# IotaWatt4_8.net
KiCad netlist of a schematic drawn in EAGLE
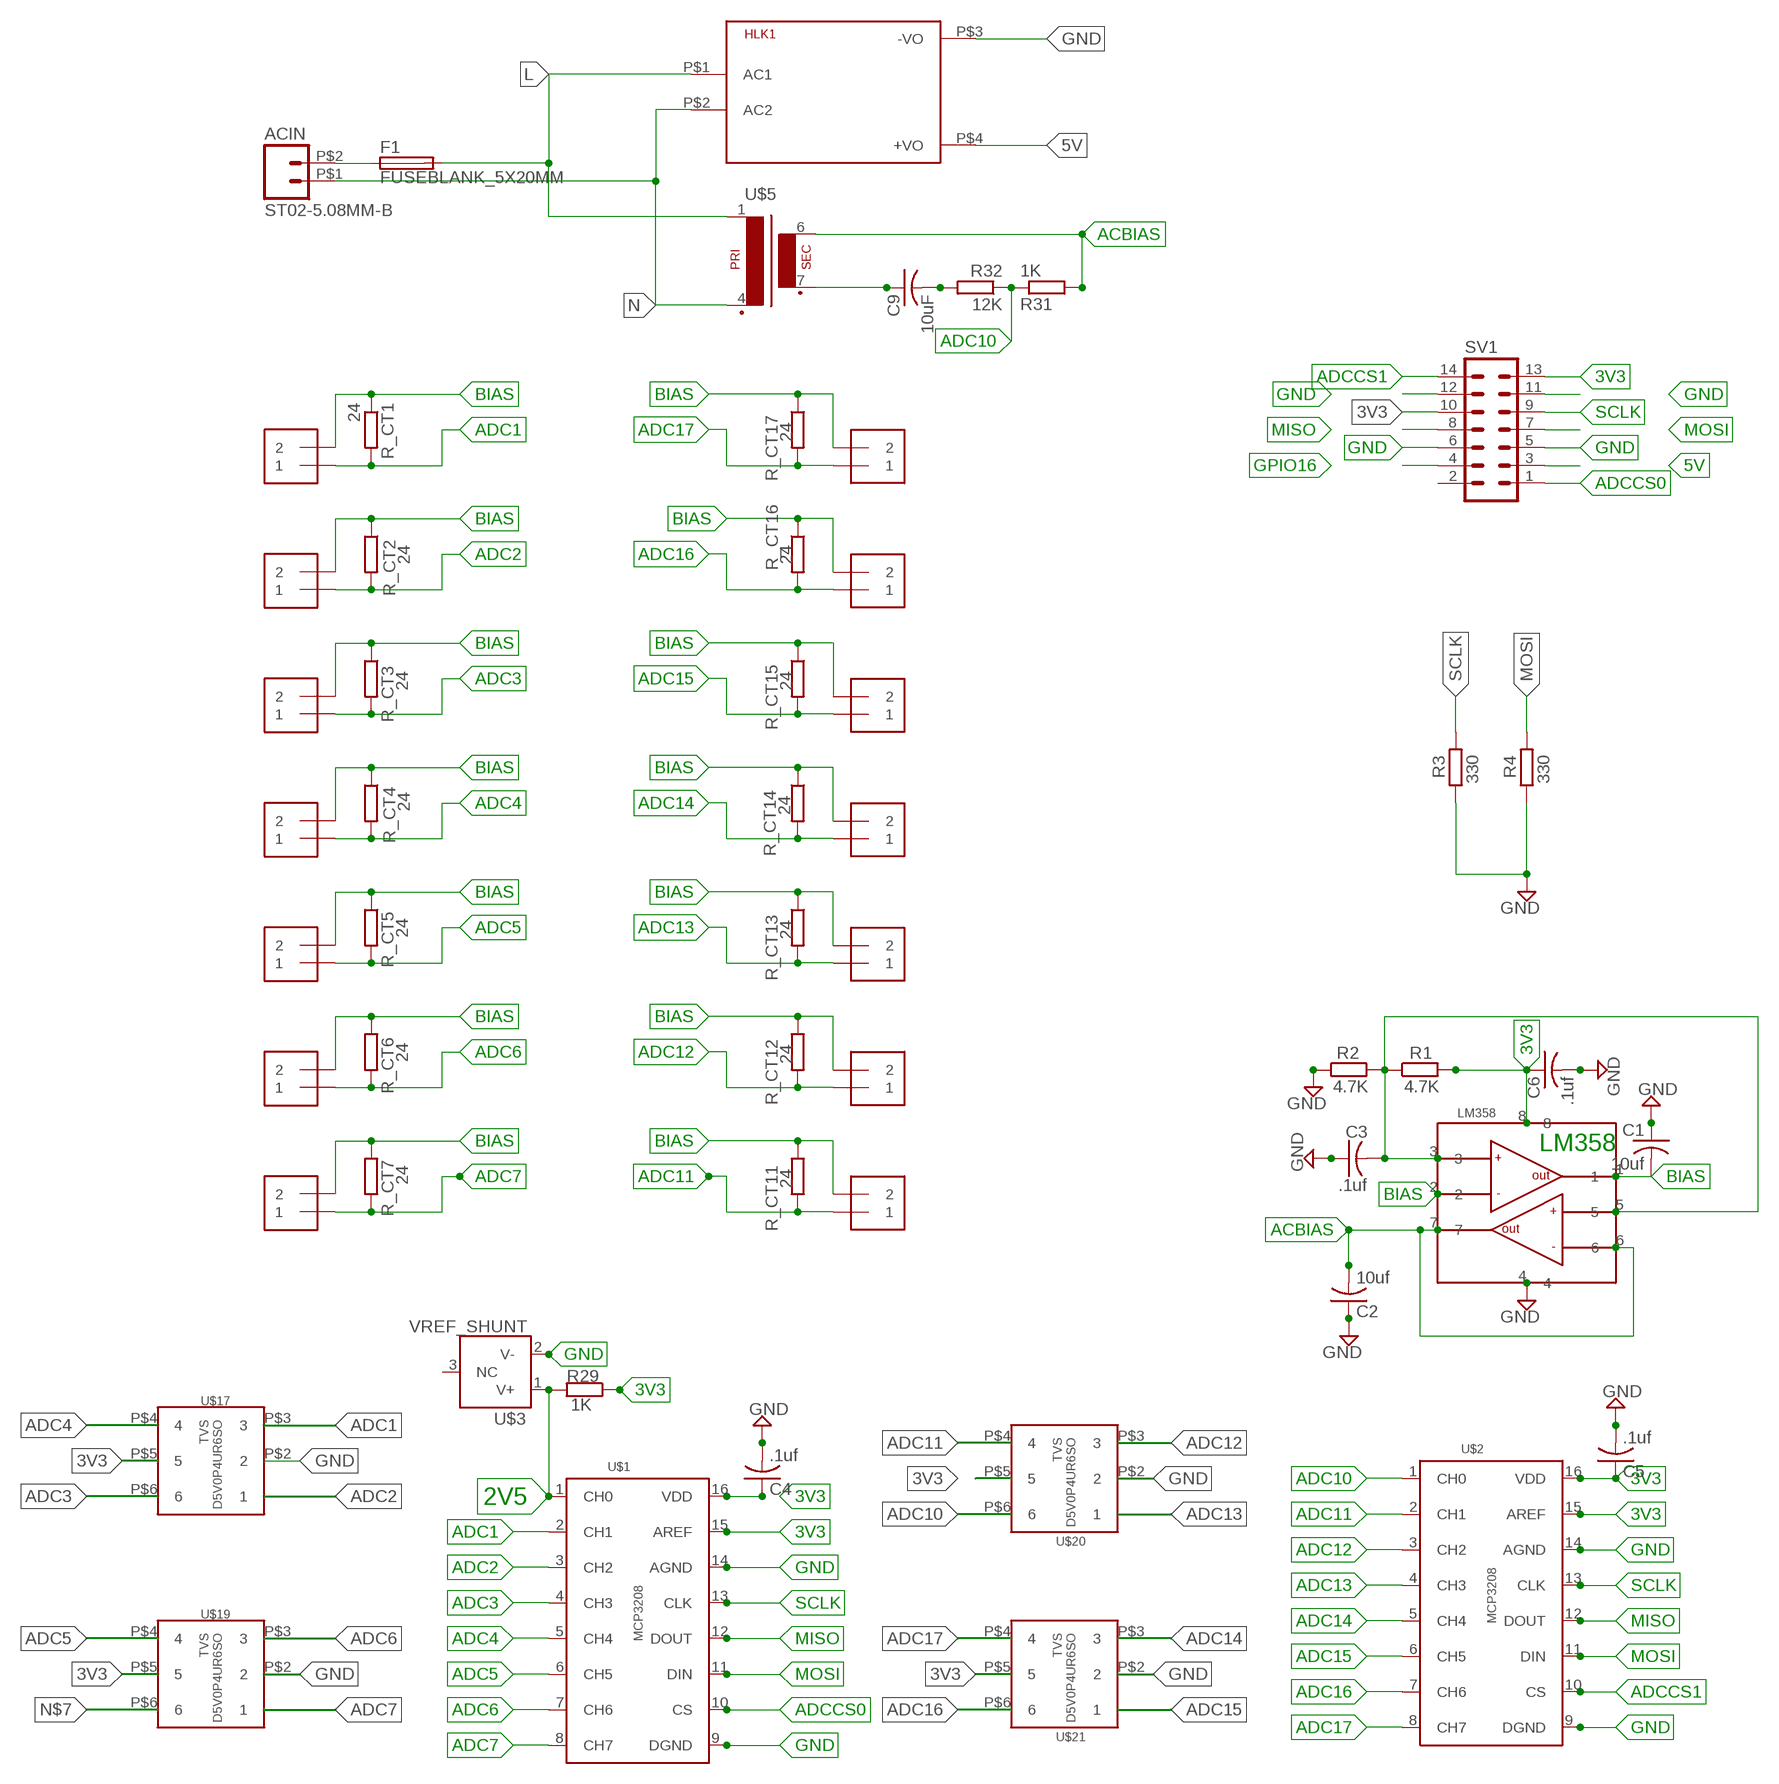
[diagram p0: schematic, sheet 1]

(export (version "E")
  (design (tool "Eeschema 10.0.6"))
  (components
    (comp (ref "ACIN")
      (value "ST02-5.08MM-B")
      (footprint "eagle-import:EK500V4R-B")
      (libsource (lib "eagle-import") (part "ST02-5.08MM-B"))
    )
    (comp (ref "C1")
      (value "10uf")
      (footprint "eagle-import:C0805")
      (libsource (lib "eagle-import") (part "C-USC0805"))
    )
    (comp (ref "C2")
      (value "10uf")
      (footprint "eagle-import:C0805")
      (libsource (lib "eagle-import") (part "C-USC0805"))
    )
    (comp (ref "C3")
      (value ".1uf")
      (footprint "eagle-import:C0805")
      (libsource (lib "eagle-import") (part "C-USC0805"))
    )
    (comp (ref "C4")
      (value ".1uf")
      (footprint "eagle-import:C0805")
      (libsource (lib "eagle-import") (part "C-USC0805"))
    )
    (comp (ref "C5")
      (value ".1uf")
      (footprint "eagle-import:C0805")
      (libsource (lib "eagle-import") (part "C-USC0805"))
    )
    (comp (ref "C6")
      (value ".1uf")
      (footprint "eagle-import:C0805")
      (libsource (lib "eagle-import") (part "C-USC0805"))
    )
    (comp (ref "C9")
      (value "10uF")
      (footprint "eagle-import:C0805")
      (libsource (lib "eagle-import") (part "C-USC0805"))
    )
    (comp (ref "CT1")
      (value "1X2-3.5MM")
      (footprint "eagle-import:3.5MMTERM")
      (libsource (lib "eagle-import") (part "1X2-3.5MM"))
    )
    (comp (ref "CT2")
      (value "1X2-3.5MM")
      (footprint "eagle-import:3.5MMTERM")
      (libsource (lib "eagle-import") (part "1X2-3.5MM"))
    )
    (comp (ref "CT3")
      (value "1X2-3.5MM")
      (footprint "eagle-import:3.5MMTERM")
      (libsource (lib "eagle-import") (part "1X2-3.5MM"))
    )
    (comp (ref "CT4")
      (value "1X2-3.5MM")
      (footprint "eagle-import:3.5MMTERM")
      (libsource (lib "eagle-import") (part "1X2-3.5MM"))
    )
    (comp (ref "CT5")
      (value "1X2-3.5MM")
      (footprint "eagle-import:3.5MMTERM")
      (libsource (lib "eagle-import") (part "1X2-3.5MM"))
    )
    (comp (ref "CT6")
      (value "1X2-3.5MM")
      (footprint "eagle-import:3.5MMTERM")
      (libsource (lib "eagle-import") (part "1X2-3.5MM"))
    )
    (comp (ref "CT7")
      (value "1X2-3.5MM")
      (footprint "eagle-import:3.5MMTERM")
      (libsource (lib "eagle-import") (part "1X2-3.5MM"))
    )
    (comp (ref "CT11")
      (value "1X2-3.5MM")
      (footprint "eagle-import:3.5MMTERM")
      (libsource (lib "eagle-import") (part "1X2-3.5MM"))
    )
    (comp (ref "CT12")
      (value "1X2-3.5MM")
      (footprint "eagle-import:3.5MMTERM")
      (libsource (lib "eagle-import") (part "1X2-3.5MM"))
    )
    (comp (ref "CT13")
      (value "1X2-3.5MM")
      (footprint "eagle-import:3.5MMTERM")
      (libsource (lib "eagle-import") (part "1X2-3.5MM"))
    )
    (comp (ref "CT14")
      (value "1X2-3.5MM")
      (footprint "eagle-import:3.5MMTERM")
      (libsource (lib "eagle-import") (part "1X2-3.5MM"))
    )
    (comp (ref "CT15")
      (value "1X2-3.5MM")
      (footprint "eagle-import:3.5MMTERM")
      (libsource (lib "eagle-import") (part "1X2-3.5MM"))
    )
    (comp (ref "CT16")
      (value "1X2-3.5MM")
      (footprint "eagle-import:3.5MMTERM")
      (libsource (lib "eagle-import") (part "1X2-3.5MM"))
    )
    (comp (ref "CT17")
      (value "1X2-3.5MM")
      (footprint "eagle-import:3.5MMTERM")
      (libsource (lib "eagle-import") (part "1X2-3.5MM"))
    )
    (comp (ref "F1")
      (value "FUSEBLANK_5X20MM")
      (footprint "eagle-import:FUSE_HOLDER_5X20MM")
      (libsource (lib "eagle-import") (part "FUSEBLANK_5X20MM"))
    )
    (comp (ref "HLK1")
      (value "HLK-PM013W")
      (footprint "eagle-import:HLK-PM01")
      (libsource (lib "eagle-import") (part "HLK-PM013W"))
    )
    (comp (ref "R1")
      (value "4.7K")
      (footprint "eagle-import:R0805")
      (libsource (lib "eagle-import") (part "R-EU_R0805"))
    )
    (comp (ref "R2")
      (value "4.7K")
      (footprint "eagle-import:R0805")
      (libsource (lib "eagle-import") (part "R-EU_R0805"))
    )
    (comp (ref "R3")
      (value "330")
      (footprint "eagle-import:R0805")
      (libsource (lib "eagle-import") (part "R-EU_R0805"))
    )
    (comp (ref "R4")
      (value "330")
      (footprint "eagle-import:R0805")
      (libsource (lib "eagle-import") (part "R-EU_R0805"))
    )
    (comp (ref "R29")
      (value "1K")
      (footprint "eagle-import:R0805")
      (libsource (lib "eagle-import") (part "R-EU_R0805"))
    )
    (comp (ref "R31")
      (value "1K")
      (footprint "eagle-import:R0805")
      (libsource (lib "eagle-import") (part "R-EU_R0805"))
    )
    (comp (ref "R32")
      (value "12K")
      (footprint "eagle-import:R0805")
      (libsource (lib "eagle-import") (part "R-EU_R0805"))
    )
    (comp (ref "R_CT1")
      (value "24")
      (footprint "eagle-import:R0805")
      (libsource (lib "eagle-import") (part "R-EU_R0805"))
    )
    (comp (ref "R_CT2")
      (value "24")
      (footprint "eagle-import:R0805")
      (libsource (lib "eagle-import") (part "R-EU_R0805"))
    )
    (comp (ref "R_CT3")
      (value "24")
      (footprint "eagle-import:R0805")
      (libsource (lib "eagle-import") (part "R-EU_R0805"))
    )
    (comp (ref "R_CT4")
      (value "24")
      (footprint "eagle-import:R0805")
      (libsource (lib "eagle-import") (part "R-EU_R0805"))
    )
    (comp (ref "R_CT5")
      (value "24")
      (footprint "eagle-import:R0805")
      (libsource (lib "eagle-import") (part "R-EU_R0805"))
    )
    (comp (ref "R_CT6")
      (value "24")
      (footprint "eagle-import:R0805")
      (libsource (lib "eagle-import") (part "R-EU_R0805"))
    )
    (comp (ref "R_CT7")
      (value "24")
      (footprint "eagle-import:R0805")
      (libsource (lib "eagle-import") (part "R-EU_R0805"))
    )
    (comp (ref "R_CT11")
      (value "24")
      (footprint "eagle-import:R0805")
      (libsource (lib "eagle-import") (part "R-EU_R0805"))
    )
    (comp (ref "R_CT12")
      (value "24")
      (footprint "eagle-import:R0805")
      (libsource (lib "eagle-import") (part "R-EU_R0805"))
    )
    (comp (ref "R_CT13")
      (value "24")
      (footprint "eagle-import:R0805")
      (libsource (lib "eagle-import") (part "R-EU_R0805"))
    )
    (comp (ref "R_CT14")
      (value "24")
      (footprint "eagle-import:R0805")
      (libsource (lib "eagle-import") (part "R-EU_R0805"))
    )
    (comp (ref "R_CT15")
      (value "24")
      (footprint "eagle-import:R0805")
      (libsource (lib "eagle-import") (part "R-EU_R0805"))
    )
    (comp (ref "R_CT16")
      (value "24")
      (footprint "eagle-import:R0805")
      (libsource (lib "eagle-import") (part "R-EU_R0805"))
    )
    (comp (ref "R_CT17")
      (value "24")
      (footprint "eagle-import:R0805")
      (libsource (lib "eagle-import") (part "R-EU_R0805"))
    )
    (comp (ref "SV1")
      (value "MA07-2")
      (footprint "eagle-import:MA07-2")
      (libsource (lib "eagle-import") (part "MA07-2"))
    )
    (comp (ref "U$1")
      (value "MCP3208")
      (footprint "eagle-import:SOIC_16")
      (libsource (lib "eagle-import") (part "MCP3208"))
    )
    (comp (ref "U$2")
      (value "MCP3208")
      (footprint "eagle-import:SOIC_16")
      (libsource (lib "eagle-import") (part "MCP3208"))
    )
    (comp (ref "U$3")
      (value "VREF_SHUNT")
      (footprint "eagle-import:SOT23_3")
      (libsource (lib "eagle-import") (part "VREF_SHUNT"))
    )
    (comp (ref "U$5")
      (value "BV20_1P1S")
      (footprint "eagle-import:BV20")
      (libsource (lib "eagle-import") (part "BV20_1P1S"))
    )
    (comp (ref "U$17")
      (value "TVS_4CHAN_ARRAYSC-74")
      (footprint "eagle-import:SC-74")
      (libsource (lib "eagle-import") (part "TVS_4CHAN_ARRAYSC-74"))
    )
    (comp (ref "U$19")
      (value "TVS_4CHAN_ARRAYSC-74")
      (footprint "eagle-import:SC-74")
      (libsource (lib "eagle-import") (part "TVS_4CHAN_ARRAYSC-74"))
    )
    (comp (ref "U$20")
      (value "TVS_4CHAN_ARRAYSC-74")
      (footprint "eagle-import:SC-74")
      (libsource (lib "eagle-import") (part "TVS_4CHAN_ARRAYSC-74"))
    )
    (comp (ref "U$21")
      (value "TVS_4CHAN_ARRAYSC-74")
      (footprint "eagle-import:SC-74")
      (libsource (lib "eagle-import") (part "TVS_4CHAN_ARRAYSC-74"))
    )
    (comp (ref "U$22")
      (value "LM358_DUAL_OP-AMP")
      (footprint "eagle-import:SOIC_8")
      (libsource (lib "eagle-import") (part "LM358_DUAL_OP-AMP"))
    )
  )
  (nets
    (net (code "1") (name "2V5") (class "Default")
      (node (ref "R29") (pin "2") (pinfunction "2_2") (pintype "passive"))
      (node (ref "U$1") (pin "1") (pinfunction "CH0_1") (pintype "input"))
      (node (ref "U$3") (pin "1") (pinfunction "V+_1") (pintype "bidirectional"))
    )
    (net (code "2") (name "3V3") (class "Default")
      (node (ref "C4") (pin "1") (pinfunction "1_1") (pintype "passive"))
      (node (ref "C5") (pin "1") (pinfunction "1_1") (pintype "passive"))
      (node (ref "C6") (pin "1") (pinfunction "1_1") (pintype "passive"))
      (node (ref "R1") (pin "2") (pinfunction "2_2") (pintype "passive"))
      (node (ref "R29") (pin "1") (pinfunction "1_1") (pintype "passive"))
      (node (ref "SV1") (pin "10") (pinfunction "10_10") (pintype "passive"))
      (node (ref "SV1") (pin "13") (pinfunction "13_13") (pintype "passive"))
      (node (ref "U$1") (pin "15") (pinfunction "AREF_15") (pintype "input"))
      (node (ref "U$1") (pin "16") (pinfunction "VDD_16") (pintype "bidirectional"))
      (node (ref "U$17") (pin "P$5") (pinfunction "5_P$5") (pintype "bidirectional"))
      (node (ref "U$19") (pin "P$5") (pinfunction "5_P$5") (pintype "bidirectional"))
      (node (ref "U$2") (pin "15") (pinfunction "AREF_15") (pintype "input"))
      (node (ref "U$2") (pin "16") (pinfunction "VDD_16") (pintype "bidirectional"))
      (node (ref "U$20") (pin "P$5") (pinfunction "5_P$5") (pintype "bidirectional"))
      (node (ref "U$21") (pin "P$5") (pinfunction "5_P$5") (pintype "bidirectional"))
      (node (ref "U$22") (pin "8") (pinfunction "8_8") (pintype "bidirectional"))
    )
    (net (code "3") (name "5V") (class "Default")
      (node (ref "HLK1") (pin "P$4") (pinfunction "+VO_P$4") (pintype "bidirectional"))
      (node (ref "SV1") (pin "3") (pinfunction "3_3") (pintype "passive"))
    )
    (net (code "4") (name "ACBIAS") (class "Default")
      (node (ref "C2") (pin "2") (pinfunction "2_2") (pintype "passive"))
      (node (ref "R31") (pin "2") (pinfunction "2_2") (pintype "passive"))
      (node (ref "U$22") (pin "6") (pinfunction "6_6") (pintype "bidirectional"))
      (node (ref "U$22") (pin "7") (pinfunction "7_7") (pintype "bidirectional"))
      (node (ref "U$5") (pin "6") (pinfunction "S4_6") (pintype "passive"))
    )
    (net (code "5") (name "ADC1") (class "Default")
      (node (ref "CT1") (pin "1") (pinfunction "1_1") (pintype "passive"))
      (node (ref "R_CT1") (pin "2") (pinfunction "2_2") (pintype "passive"))
      (node (ref "U$1") (pin "2") (pinfunction "CH1_2") (pintype "input"))
      (node (ref "U$17") (pin "P$3") (pinfunction "3_P$3") (pintype "bidirectional"))
    )
    (net (code "6") (name "ADC2") (class "Default")
      (node (ref "CT2") (pin "1") (pinfunction "1_1") (pintype "passive"))
      (node (ref "R_CT2") (pin "2") (pinfunction "2_2") (pintype "passive"))
      (node (ref "U$1") (pin "3") (pinfunction "CH2_3") (pintype "input"))
      (node (ref "U$17") (pin "P$1") (pinfunction "1_P$1") (pintype "bidirectional"))
    )
    (net (code "7") (name "ADC3") (class "Default")
      (node (ref "CT3") (pin "1") (pinfunction "1_1") (pintype "passive"))
      (node (ref "R_CT3") (pin "2") (pinfunction "2_2") (pintype "passive"))
      (node (ref "U$1") (pin "4") (pinfunction "CH3_4") (pintype "input"))
      (node (ref "U$17") (pin "P$6") (pinfunction "6_P$6") (pintype "bidirectional"))
    )
    (net (code "8") (name "ADC4") (class "Default")
      (node (ref "CT4") (pin "1") (pinfunction "1_1") (pintype "passive"))
      (node (ref "R_CT4") (pin "2") (pinfunction "2_2") (pintype "passive"))
      (node (ref "U$1") (pin "5") (pinfunction "CH4_5") (pintype "bidirectional"))
      (node (ref "U$17") (pin "P$4") (pinfunction "4_P$4") (pintype "bidirectional"))
    )
    (net (code "9") (name "ADC5") (class "Default")
      (node (ref "CT5") (pin "1") (pinfunction "1_1") (pintype "passive"))
      (node (ref "R_CT5") (pin "2") (pinfunction "2_2") (pintype "passive"))
      (node (ref "U$1") (pin "6") (pinfunction "CH5_6") (pintype "bidirectional"))
      (node (ref "U$19") (pin "P$4") (pinfunction "4_P$4") (pintype "bidirectional"))
    )
    (net (code "10") (name "ADC6") (class "Default")
      (node (ref "CT6") (pin "1") (pinfunction "1_1") (pintype "passive"))
      (node (ref "R_CT6") (pin "2") (pinfunction "2_2") (pintype "passive"))
      (node (ref "U$1") (pin "7") (pinfunction "CH6_7") (pintype "input"))
      (node (ref "U$19") (pin "P$3") (pinfunction "3_P$3") (pintype "bidirectional"))
    )
    (net (code "11") (name "ADC7") (class "Default")
      (node (ref "CT7") (pin "1") (pinfunction "1_1") (pintype "passive"))
      (node (ref "R_CT7") (pin "2") (pinfunction "2_2") (pintype "passive"))
      (node (ref "U$1") (pin "8") (pinfunction "CH7_8") (pintype "bidirectional"))
      (node (ref "U$19") (pin "P$1") (pinfunction "1_P$1") (pintype "bidirectional"))
    )
    (net (code "12") (name "ADC10") (class "Default")
      (node (ref "R31") (pin "1") (pinfunction "1_1") (pintype "passive"))
      (node (ref "R32") (pin "1") (pinfunction "1_1") (pintype "passive"))
      (node (ref "U$2") (pin "1") (pinfunction "CH0_1") (pintype "input"))
      (node (ref "U$20") (pin "P$6") (pinfunction "6_P$6") (pintype "bidirectional"))
    )
    (net (code "13") (name "ADC11") (class "Default")
      (node (ref "CT11") (pin "1") (pinfunction "1_1") (pintype "passive"))
      (node (ref "R_CT11") (pin "2") (pinfunction "2_2") (pintype "passive"))
      (node (ref "U$2") (pin "2") (pinfunction "CH1_2") (pintype "input"))
      (node (ref "U$20") (pin "P$4") (pinfunction "4_P$4") (pintype "bidirectional"))
    )
    (net (code "14") (name "ADC12") (class "Default")
      (node (ref "CT12") (pin "1") (pinfunction "1_1") (pintype "passive"))
      (node (ref "R_CT12") (pin "2") (pinfunction "2_2") (pintype "passive"))
      (node (ref "U$2") (pin "3") (pinfunction "CH2_3") (pintype "input"))
      (node (ref "U$20") (pin "P$3") (pinfunction "3_P$3") (pintype "bidirectional"))
    )
    (net (code "15") (name "ADC13") (class "Default")
      (node (ref "CT13") (pin "1") (pinfunction "1_1") (pintype "passive"))
      (node (ref "R_CT13") (pin "2") (pinfunction "2_2") (pintype "passive"))
      (node (ref "U$2") (pin "4") (pinfunction "CH3_4") (pintype "input"))
      (node (ref "U$20") (pin "P$1") (pinfunction "1_P$1") (pintype "bidirectional"))
    )
    (net (code "16") (name "ADC14") (class "Default")
      (node (ref "CT14") (pin "1") (pinfunction "1_1") (pintype "passive"))
      (node (ref "R_CT14") (pin "2") (pinfunction "2_2") (pintype "passive"))
      (node (ref "U$2") (pin "5") (pinfunction "CH4_5") (pintype "bidirectional"))
      (node (ref "U$21") (pin "P$3") (pinfunction "3_P$3") (pintype "bidirectional"))
    )
    (net (code "17") (name "ADC15") (class "Default")
      (node (ref "CT15") (pin "1") (pinfunction "1_1") (pintype "passive"))
      (node (ref "R_CT15") (pin "2") (pinfunction "2_2") (pintype "passive"))
      (node (ref "U$2") (pin "6") (pinfunction "CH5_6") (pintype "bidirectional"))
      (node (ref "U$21") (pin "P$1") (pinfunction "1_P$1") (pintype "bidirectional"))
    )
    (net (code "18") (name "ADC16") (class "Default")
      (node (ref "CT16") (pin "1") (pinfunction "1_1") (pintype "passive"))
      (node (ref "R_CT16") (pin "2") (pinfunction "2_2") (pintype "passive"))
      (node (ref "U$2") (pin "7") (pinfunction "CH6_7") (pintype "input"))
      (node (ref "U$21") (pin "P$6") (pinfunction "6_P$6") (pintype "bidirectional"))
    )
    (net (code "19") (name "ADC17") (class "Default")
      (node (ref "CT17") (pin "1") (pinfunction "1_1") (pintype "passive"))
      (node (ref "R_CT17") (pin "2") (pinfunction "2_2") (pintype "passive"))
      (node (ref "U$2") (pin "8") (pinfunction "CH7_8") (pintype "bidirectional"))
      (node (ref "U$21") (pin "P$4") (pinfunction "4_P$4") (pintype "bidirectional"))
    )
    (net (code "20") (name "ADCCS0") (class "Default")
      (node (ref "SV1") (pin "1") (pinfunction "1_1") (pintype "passive"))
      (node (ref "U$1") (pin "10") (pinfunction "CS_10") (pintype "input"))
    )
    (net (code "21") (name "ADCCS1") (class "Default")
      (node (ref "SV1") (pin "14") (pinfunction "14_14") (pintype "passive"))
      (node (ref "U$2") (pin "10") (pinfunction "CS_10") (pintype "input"))
    )
    (net (code "22") (name "BIAS") (class "Default")
      (node (ref "C1") (pin "2") (pinfunction "2_2") (pintype "passive"))
      (node (ref "CT1") (pin "2") (pinfunction "2_2") (pintype "passive"))
      (node (ref "CT11") (pin "2") (pinfunction "2_2") (pintype "passive"))
      (node (ref "CT12") (pin "2") (pinfunction "2_2") (pintype "passive"))
      (node (ref "CT13") (pin "2") (pinfunction "2_2") (pintype "passive"))
      (node (ref "CT14") (pin "2") (pinfunction "2_2") (pintype "passive"))
      (node (ref "CT15") (pin "2") (pinfunction "2_2") (pintype "passive"))
      (node (ref "CT16") (pin "2") (pinfunction "2_2") (pintype "passive"))
      (node (ref "CT17") (pin "2") (pinfunction "2_2") (pintype "passive"))
      (node (ref "CT2") (pin "2") (pinfunction "2_2") (pintype "passive"))
      (node (ref "CT3") (pin "2") (pinfunction "2_2") (pintype "passive"))
      (node (ref "CT4") (pin "2") (pinfunction "2_2") (pintype "passive"))
      (node (ref "CT5") (pin "2") (pinfunction "2_2") (pintype "passive"))
      (node (ref "CT6") (pin "2") (pinfunction "2_2") (pintype "passive"))
      (node (ref "CT7") (pin "2") (pinfunction "2_2") (pintype "passive"))
      (node (ref "R_CT1") (pin "1") (pinfunction "1_1") (pintype "passive"))
      (node (ref "R_CT11") (pin "1") (pinfunction "1_1") (pintype "passive"))
      (node (ref "R_CT12") (pin "1") (pinfunction "1_1") (pintype "passive"))
      (node (ref "R_CT13") (pin "1") (pinfunction "1_1") (pintype "passive"))
      (node (ref "R_CT14") (pin "1") (pinfunction "1_1") (pintype "passive"))
      (node (ref "R_CT15") (pin "1") (pinfunction "1_1") (pintype "passive"))
      (node (ref "R_CT16") (pin "1") (pinfunction "1_1") (pintype "passive"))
      (node (ref "R_CT17") (pin "1") (pinfunction "1_1") (pintype "passive"))
      (node (ref "R_CT2") (pin "1") (pinfunction "1_1") (pintype "passive"))
      (node (ref "R_CT3") (pin "1") (pinfunction "1_1") (pintype "passive"))
      (node (ref "R_CT4") (pin "1") (pinfunction "1_1") (pintype "passive"))
      (node (ref "R_CT5") (pin "1") (pinfunction "1_1") (pintype "passive"))
      (node (ref "R_CT6") (pin "1") (pinfunction "1_1") (pintype "passive"))
      (node (ref "R_CT7") (pin "1") (pinfunction "1_1") (pintype "passive"))
      (node (ref "U$22") (pin "1") (pinfunction "1_1") (pintype "bidirectional"))
      (node (ref "U$22") (pin "2") (pinfunction "2_2") (pintype "bidirectional"))
    )
    (net (code "23") (name "GND") (class "Default")
      (node (ref "C1") (pin "1") (pinfunction "1_1") (pintype "passive"))
      (node (ref "C2") (pin "1") (pinfunction "1_1") (pintype "passive"))
      (node (ref "C3") (pin "1") (pinfunction "1_1") (pintype "passive"))
      (node (ref "C4") (pin "2") (pinfunction "2_2") (pintype "passive"))
      (node (ref "C5") (pin "2") (pinfunction "2_2") (pintype "passive"))
      (node (ref "C6") (pin "2") (pinfunction "2_2") (pintype "passive"))
      (node (ref "HLK1") (pin "P$3") (pinfunction "-VO_P$3") (pintype "bidirectional"))
      (node (ref "R2") (pin "1") (pinfunction "1_1") (pintype "passive"))
      (node (ref "R3") (pin "1") (pinfunction "1_1") (pintype "passive"))
      (node (ref "R4") (pin "1") (pinfunction "1_1") (pintype "passive"))
      (node (ref "SV1") (pin "11") (pinfunction "11_11") (pintype "passive"))
      (node (ref "SV1") (pin "12") (pinfunction "12_12") (pintype "passive"))
      (node (ref "SV1") (pin "5") (pinfunction "5_5") (pintype "passive"))
      (node (ref "SV1") (pin "6") (pinfunction "6_6") (pintype "passive"))
      (node (ref "U$1") (pin "14") (pinfunction "AGND_14") (pintype "input"))
      (node (ref "U$1") (pin "9") (pinfunction "DGND_9") (pintype "bidirectional"))
      (node (ref "U$17") (pin "P$2") (pinfunction "2_P$2") (pintype "bidirectional"))
      (node (ref "U$19") (pin "P$2") (pinfunction "2_P$2") (pintype "bidirectional"))
      (node (ref "U$2") (pin "14") (pinfunction "AGND_14") (pintype "input"))
      (node (ref "U$2") (pin "9") (pinfunction "DGND_9") (pintype "bidirectional"))
      (node (ref "U$20") (pin "P$2") (pinfunction "2_P$2") (pintype "bidirectional"))
      (node (ref "U$21") (pin "P$2") (pinfunction "2_P$2") (pintype "bidirectional"))
      (node (ref "U$22") (pin "4") (pinfunction "4_4") (pintype "bidirectional"))
      (node (ref "U$3") (pin "2") (pinfunction "V-_2") (pintype "bidirectional"))
    )
    (net (code "24") (name "GPIO16") (class "Default")
      (node (ref "SV1") (pin "4") (pinfunction "4_4") (pintype "passive"))
    )
    (net (code "25") (name "L") (class "Default")
      (node (ref "F1") (pin "2") (pinfunction "2_2") (pintype "passive"))
      (node (ref "HLK1") (pin "P$1") (pinfunction "AC1_P$1") (pintype "bidirectional"))
      (node (ref "U$5") (pin "1") (pinfunction "P1_1") (pintype "passive"))
    )
    (net (code "26") (name "MISO") (class "Default")
      (node (ref "SV1") (pin "8") (pinfunction "8_8") (pintype "passive"))
      (node (ref "U$1") (pin "12") (pinfunction "DOUT_12") (pintype "bidirectional"))
      (node (ref "U$2") (pin "12") (pinfunction "DOUT_12") (pintype "bidirectional"))
    )
    (net (code "27") (name "MOSI") (class "Default")
      (node (ref "R4") (pin "2") (pinfunction "2_2") (pintype "passive"))
      (node (ref "SV1") (pin "7") (pinfunction "7_7") (pintype "passive"))
      (node (ref "U$1") (pin "11") (pinfunction "DIN_11") (pintype "input"))
      (node (ref "U$2") (pin "11") (pinfunction "DIN_11") (pintype "input"))
    )
    (net (code "28") (name "N") (class "Default")
      (node (ref "ACIN") (pin "P$1") (pinfunction "1_P$1") (pintype "passive"))
      (node (ref "HLK1") (pin "P$2") (pinfunction "AC2_P$2") (pintype "bidirectional"))
      (node (ref "U$5") (pin "4") (pinfunction "P2_4") (pintype "passive"))
    )
    (net (code "29") (name "N$7") (class "Default")
      (node (ref "U$19") (pin "P$6") (pinfunction "6_P$6") (pintype "bidirectional"))
    )
    (net (code "30") (name "Net-(ACIN-2)") (class "Default")
      (node (ref "ACIN") (pin "P$2") (pinfunction "2_P$2") (pintype "passive"))
      (node (ref "F1") (pin "1") (pinfunction "1_1") (pintype "passive"))
    )
    (net (code "31") (name "Net-(C3-Pad2)") (class "Default")
      (node (ref "C3") (pin "2") (pinfunction "2_2") (pintype "passive"))
      (node (ref "R1") (pin "1") (pinfunction "1_1") (pintype "passive"))
      (node (ref "R2") (pin "2") (pinfunction "2_2") (pintype "passive"))
      (node (ref "U$22") (pin "3") (pinfunction "3_3") (pintype "bidirectional"))
      (node (ref "U$22") (pin "5") (pinfunction "5_5") (pintype "bidirectional"))
    )
    (net (code "32") (name "Net-(C9-Pad2)") (class "Default")
      (node (ref "C9") (pin "2") (pinfunction "2_2") (pintype "passive"))
      (node (ref "R32") (pin "2") (pinfunction "2_2") (pintype "passive"))
    )
    (net (code "33") (name "Net-(U$5-S3)") (class "Default")
      (node (ref "C9") (pin "1") (pinfunction "1_1") (pintype "passive"))
      (node (ref "U$5") (pin "7") (pinfunction "S3_7") (pintype "passive"))
    )
    (net (code "34") (name "SCLK") (class "Default")
      (node (ref "R3") (pin "2") (pinfunction "2_2") (pintype "passive"))
      (node (ref "SV1") (pin "9") (pinfunction "9_9") (pintype "passive"))
      (node (ref "U$1") (pin "13") (pinfunction "CLK_13") (pintype "input"))
      (node (ref "U$2") (pin "13") (pinfunction "CLK_13") (pintype "input"))
    )
    (net (code "35") (name "unconnected-(SV1-Pad2)") (class "Default")
      (node (ref "SV1") (pin "2") (pinfunction "2_2") (pintype "passive"))
    )
    (net (code "36") (name "unconnected-(U$3-NC-Pad3)") (class "Default")
      (node (ref "U$3") (pin "3") (pinfunction "NC_3") (pintype "bidirectional"))
    )
  )
)
